# M2_KEY_M.net
KiCad netlist of a schematic drawn in Altium Designer
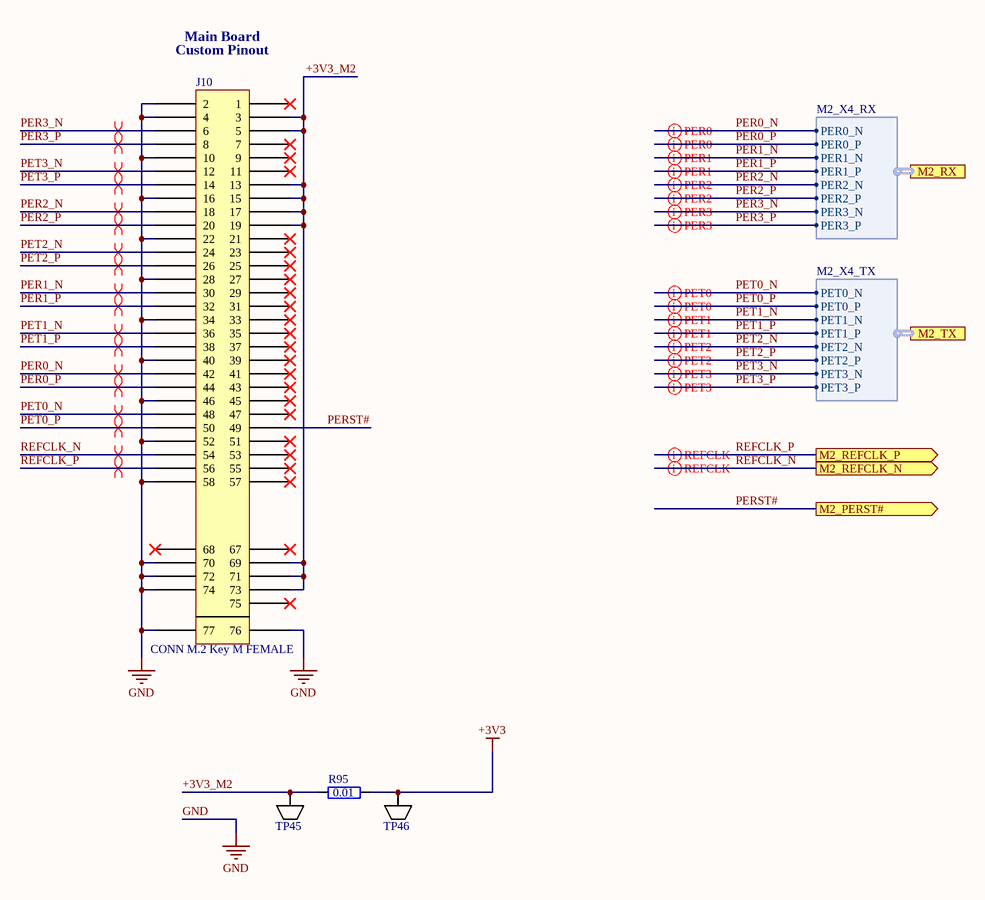
[diagram p0: M2_KEY_M.SchDoc]

(export (version "E")
  (design (tool "Eeschema 10.0.6"))
  (components
    (comp (ref "J10")
      (value "CONN M.2 Key M FEMALE")
      (footprint "TE_M2_KEYM_2199230")
      (libsource (lib "DSO") (part "CONN M.2 Key M FEMALE"))
    )
    (comp (ref "R95")
      (value "0.01")
      (footprint "GEN_R_0603")
      (fields (field (name "TOLERANCE") "1%"))
      (libsource (lib "DSO") (part "RES 0.01 OHM 1% 1/4W 0603"))
    )
    (comp (ref "TP45")
      (value "5015")
      (footprint "KEY_5015")
      (libsource (lib "DSO") (part "TP KEYSTONE 5015"))
    )
    (comp (ref "TP46")
      (value "5015")
      (footprint "KEY_5015")
      (libsource (lib "DSO") (part "TP KEYSTONE 5015"))
    )
  )
  (nets
    (net (code "3") (name "+3V3") (class "Default")
      (node (ref "R95") (pin "2") (pinfunction "2_2") (pintype "passive"))
      (node (ref "TP46") (pin "1") (pinfunction "1_1") (pintype "passive"))
    )
    (net (code "4") (name "/+3V3_M2") (class "Default")
      (node (ref "J10") (pin "13") (pinfunction "13_13") (pintype "passive"))
      (node (ref "J10") (pin "15") (pinfunction "15_15") (pintype "passive"))
      (node (ref "J10") (pin "17") (pinfunction "17_17") (pintype "passive"))
      (node (ref "J10") (pin "19") (pinfunction "19_19") (pintype "passive"))
      (node (ref "J10") (pin "3") (pinfunction "3_3") (pintype "passive"))
      (node (ref "J10") (pin "5") (pinfunction "5_5") (pintype "passive"))
      (node (ref "J10") (pin "69") (pinfunction "69_69") (pintype "passive"))
      (node (ref "J10") (pin "71") (pinfunction "71_71") (pintype "passive"))
      (node (ref "J10") (pin "73") (pinfunction "73_73") (pintype "passive"))
      (node (ref "R95") (pin "1") (pinfunction "1_1") (pintype "passive"))
      (node (ref "TP45") (pin "1") (pinfunction "1_1") (pintype "passive"))
    )
    (net (code "5") (name "/PER0_N") (class "Default")
      (node (ref "J10") (pin "42") (pinfunction "42_42") (pintype "passive"))
    )
    (net (code "6") (name "/PER0_P") (class "Default")
      (node (ref "J10") (pin "44") (pinfunction "44_44") (pintype "passive"))
    )
    (net (code "7") (name "/PER1_N") (class "Default")
      (node (ref "J10") (pin "30") (pinfunction "30_30") (pintype "passive"))
    )
    (net (code "8") (name "/PER1_P") (class "Default")
      (node (ref "J10") (pin "32") (pinfunction "32_32") (pintype "passive"))
    )
    (net (code "9") (name "/PER2_N") (class "Default")
      (node (ref "J10") (pin "18") (pinfunction "18_18") (pintype "passive"))
    )
    (net (code "10") (name "/PER2_P") (class "Default")
      (node (ref "J10") (pin "20") (pinfunction "20_20") (pintype "passive"))
    )
    (net (code "11") (name "/PER3_N") (class "Default")
      (node (ref "J10") (pin "6") (pinfunction "6_6") (pintype "passive"))
    )
    (net (code "12") (name "/PER3_P") (class "Default")
      (node (ref "J10") (pin "8") (pinfunction "8_8") (pintype "passive"))
    )
    (net (code "13") (name "/PERST#") (class "Default")
      (node (ref "J10") (pin "49") (pinfunction "49_49") (pintype "passive"))
    )
    (net (code "14") (name "/PET0_N") (class "Default")
      (node (ref "J10") (pin "48") (pinfunction "48_48") (pintype "passive"))
    )
    (net (code "15") (name "/PET0_P") (class "Default")
      (node (ref "J10") (pin "50") (pinfunction "50_50") (pintype "passive"))
    )
    (net (code "16") (name "/PET1_N") (class "Default")
      (node (ref "J10") (pin "36") (pinfunction "36_36") (pintype "passive"))
    )
    (net (code "17") (name "/PET1_P") (class "Default")
      (node (ref "J10") (pin "38") (pinfunction "38_38") (pintype "passive"))
    )
    (net (code "18") (name "/PET2_N") (class "Default")
      (node (ref "J10") (pin "24") (pinfunction "24_24") (pintype "passive"))
    )
    (net (code "19") (name "/PET2_P") (class "Default")
      (node (ref "J10") (pin "26") (pinfunction "26_26") (pintype "passive"))
    )
    (net (code "20") (name "/PET3_N") (class "Default")
      (node (ref "J10") (pin "12") (pinfunction "12_12") (pintype "passive"))
    )
    (net (code "21") (name "/PET3_P") (class "Default")
      (node (ref "J10") (pin "14") (pinfunction "14_14") (pintype "passive"))
    )
    (net (code "22") (name "/REFCLK_N") (class "Default")
      (node (ref "J10") (pin "54") (pinfunction "54_54") (pintype "passive"))
    )
    (net (code "23") (name "/REFCLK_P") (class "Default")
      (node (ref "J10") (pin "56") (pinfunction "56_56") (pintype "passive"))
    )
    (net (code "26") (name "GND") (class "Default")
      (node (ref "J10") (pin "10") (pinfunction "10_10") (pintype "passive"))
      (node (ref "J10") (pin "16") (pinfunction "16_16") (pintype "passive"))
      (node (ref "J10") (pin "2") (pinfunction "2_2") (pintype "passive"))
      (node (ref "J10") (pin "22") (pinfunction "22_22") (pintype "passive"))
      (node (ref "J10") (pin "28") (pinfunction "28_28") (pintype "passive"))
      (node (ref "J10") (pin "34") (pinfunction "34_34") (pintype "passive"))
      (node (ref "J10") (pin "4") (pinfunction "4_4") (pintype "passive"))
      (node (ref "J10") (pin "40") (pinfunction "40_40") (pintype "passive"))
      (node (ref "J10") (pin "46") (pinfunction "46_46") (pintype "passive"))
      (node (ref "J10") (pin "52") (pinfunction "52_52") (pintype "passive"))
      (node (ref "J10") (pin "58") (pinfunction "58_58") (pintype "passive"))
      (node (ref "J10") (pin "70") (pinfunction "70_70") (pintype "passive"))
      (node (ref "J10") (pin "72") (pinfunction "72_72") (pintype "passive"))
      (node (ref "J10") (pin "74") (pinfunction "74_74") (pintype "passive"))
      (node (ref "J10") (pin "76") (pinfunction "76_76") (pintype "passive"))
      (node (ref "J10") (pin "77") (pinfunction "77_77") (pintype "passive"))
    )
    (net (code "27") (name "unconnected-(J10-Pad1)") (class "Default")
      (node (ref "J10") (pin "1") (pinfunction "1_1") (pintype "passive+no_connect"))
    )
    (net (code "28") (name "unconnected-(J10-Pad7)") (class "Default")
      (node (ref "J10") (pin "7") (pinfunction "7_7") (pintype "passive+no_connect"))
    )
    (net (code "29") (name "unconnected-(J10-Pad9)") (class "Default")
      (node (ref "J10") (pin "9") (pinfunction "9_9") (pintype "passive+no_connect"))
    )
    (net (code "30") (name "unconnected-(J10-Pad11)") (class "Default")
      (node (ref "J10") (pin "11") (pinfunction "11_11") (pintype "passive+no_connect"))
    )
    (net (code "31") (name "unconnected-(J10-Pad21)") (class "Default")
      (node (ref "J10") (pin "21") (pinfunction "21_21") (pintype "passive+no_connect"))
    )
    (net (code "32") (name "unconnected-(J10-Pad23)") (class "Default")
      (node (ref "J10") (pin "23") (pinfunction "23_23") (pintype "passive+no_connect"))
    )
    (net (code "33") (name "unconnected-(J10-Pad25)") (class "Default")
      (node (ref "J10") (pin "25") (pinfunction "25_25") (pintype "passive+no_connect"))
    )
    (net (code "34") (name "unconnected-(J10-Pad27)") (class "Default")
      (node (ref "J10") (pin "27") (pinfunction "27_27") (pintype "passive+no_connect"))
    )
    (net (code "35") (name "unconnected-(J10-Pad29)") (class "Default")
      (node (ref "J10") (pin "29") (pinfunction "29_29") (pintype "passive+no_connect"))
    )
    (net (code "36") (name "unconnected-(J10-Pad31)") (class "Default")
      (node (ref "J10") (pin "31") (pinfunction "31_31") (pintype "passive+no_connect"))
    )
    (net (code "37") (name "unconnected-(J10-Pad33)") (class "Default")
      (node (ref "J10") (pin "33") (pinfunction "33_33") (pintype "passive+no_connect"))
    )
    (net (code "38") (name "unconnected-(J10-Pad35)") (class "Default")
      (node (ref "J10") (pin "35") (pinfunction "35_35") (pintype "passive+no_connect"))
    )
    (net (code "39") (name "unconnected-(J10-Pad37)") (class "Default")
      (node (ref "J10") (pin "37") (pinfunction "37_37") (pintype "passive+no_connect"))
    )
    (net (code "40") (name "unconnected-(J10-Pad39)") (class "Default")
      (node (ref "J10") (pin "39") (pinfunction "39_39") (pintype "passive+no_connect"))
    )
    (net (code "41") (name "unconnected-(J10-Pad41)") (class "Default")
      (node (ref "J10") (pin "41") (pinfunction "41_41") (pintype "passive+no_connect"))
    )
    (net (code "42") (name "unconnected-(J10-Pad43)") (class "Default")
      (node (ref "J10") (pin "43") (pinfunction "43_43") (pintype "passive+no_connect"))
    )
    (net (code "43") (name "unconnected-(J10-Pad45)") (class "Default")
      (node (ref "J10") (pin "45") (pinfunction "45_45") (pintype "passive+no_connect"))
    )
    (net (code "44") (name "unconnected-(J10-Pad47)") (class "Default")
      (node (ref "J10") (pin "47") (pinfunction "47_47") (pintype "passive+no_connect"))
    )
    (net (code "45") (name "unconnected-(J10-Pad51)") (class "Default")
      (node (ref "J10") (pin "51") (pinfunction "51_51") (pintype "passive+no_connect"))
    )
    (net (code "46") (name "unconnected-(J10-Pad53)") (class "Default")
      (node (ref "J10") (pin "53") (pinfunction "53_53") (pintype "passive+no_connect"))
    )
    (net (code "47") (name "unconnected-(J10-Pad55)") (class "Default")
      (node (ref "J10") (pin "55") (pinfunction "55_55") (pintype "passive+no_connect"))
    )
    (net (code "48") (name "unconnected-(J10-Pad57)") (class "Default")
      (node (ref "J10") (pin "57") (pinfunction "57_57") (pintype "passive+no_connect"))
    )
    (net (code "49") (name "unconnected-(J10-Pad67)") (class "Default")
      (node (ref "J10") (pin "67") (pinfunction "67_67") (pintype "passive+no_connect"))
    )
    (net (code "50") (name "unconnected-(J10-Pad68)") (class "Default")
      (node (ref "J10") (pin "68") (pinfunction "68_68") (pintype "passive+no_connect"))
    )
    (net (code "51") (name "unconnected-(J10-Pad75)") (class "Default")
      (node (ref "J10") (pin "75") (pinfunction "75_75") (pintype "passive+no_connect"))
    )
  )
)
